# diskohedron4w_revc.net
KiCad netlist of a schematic drawn in EAGLE
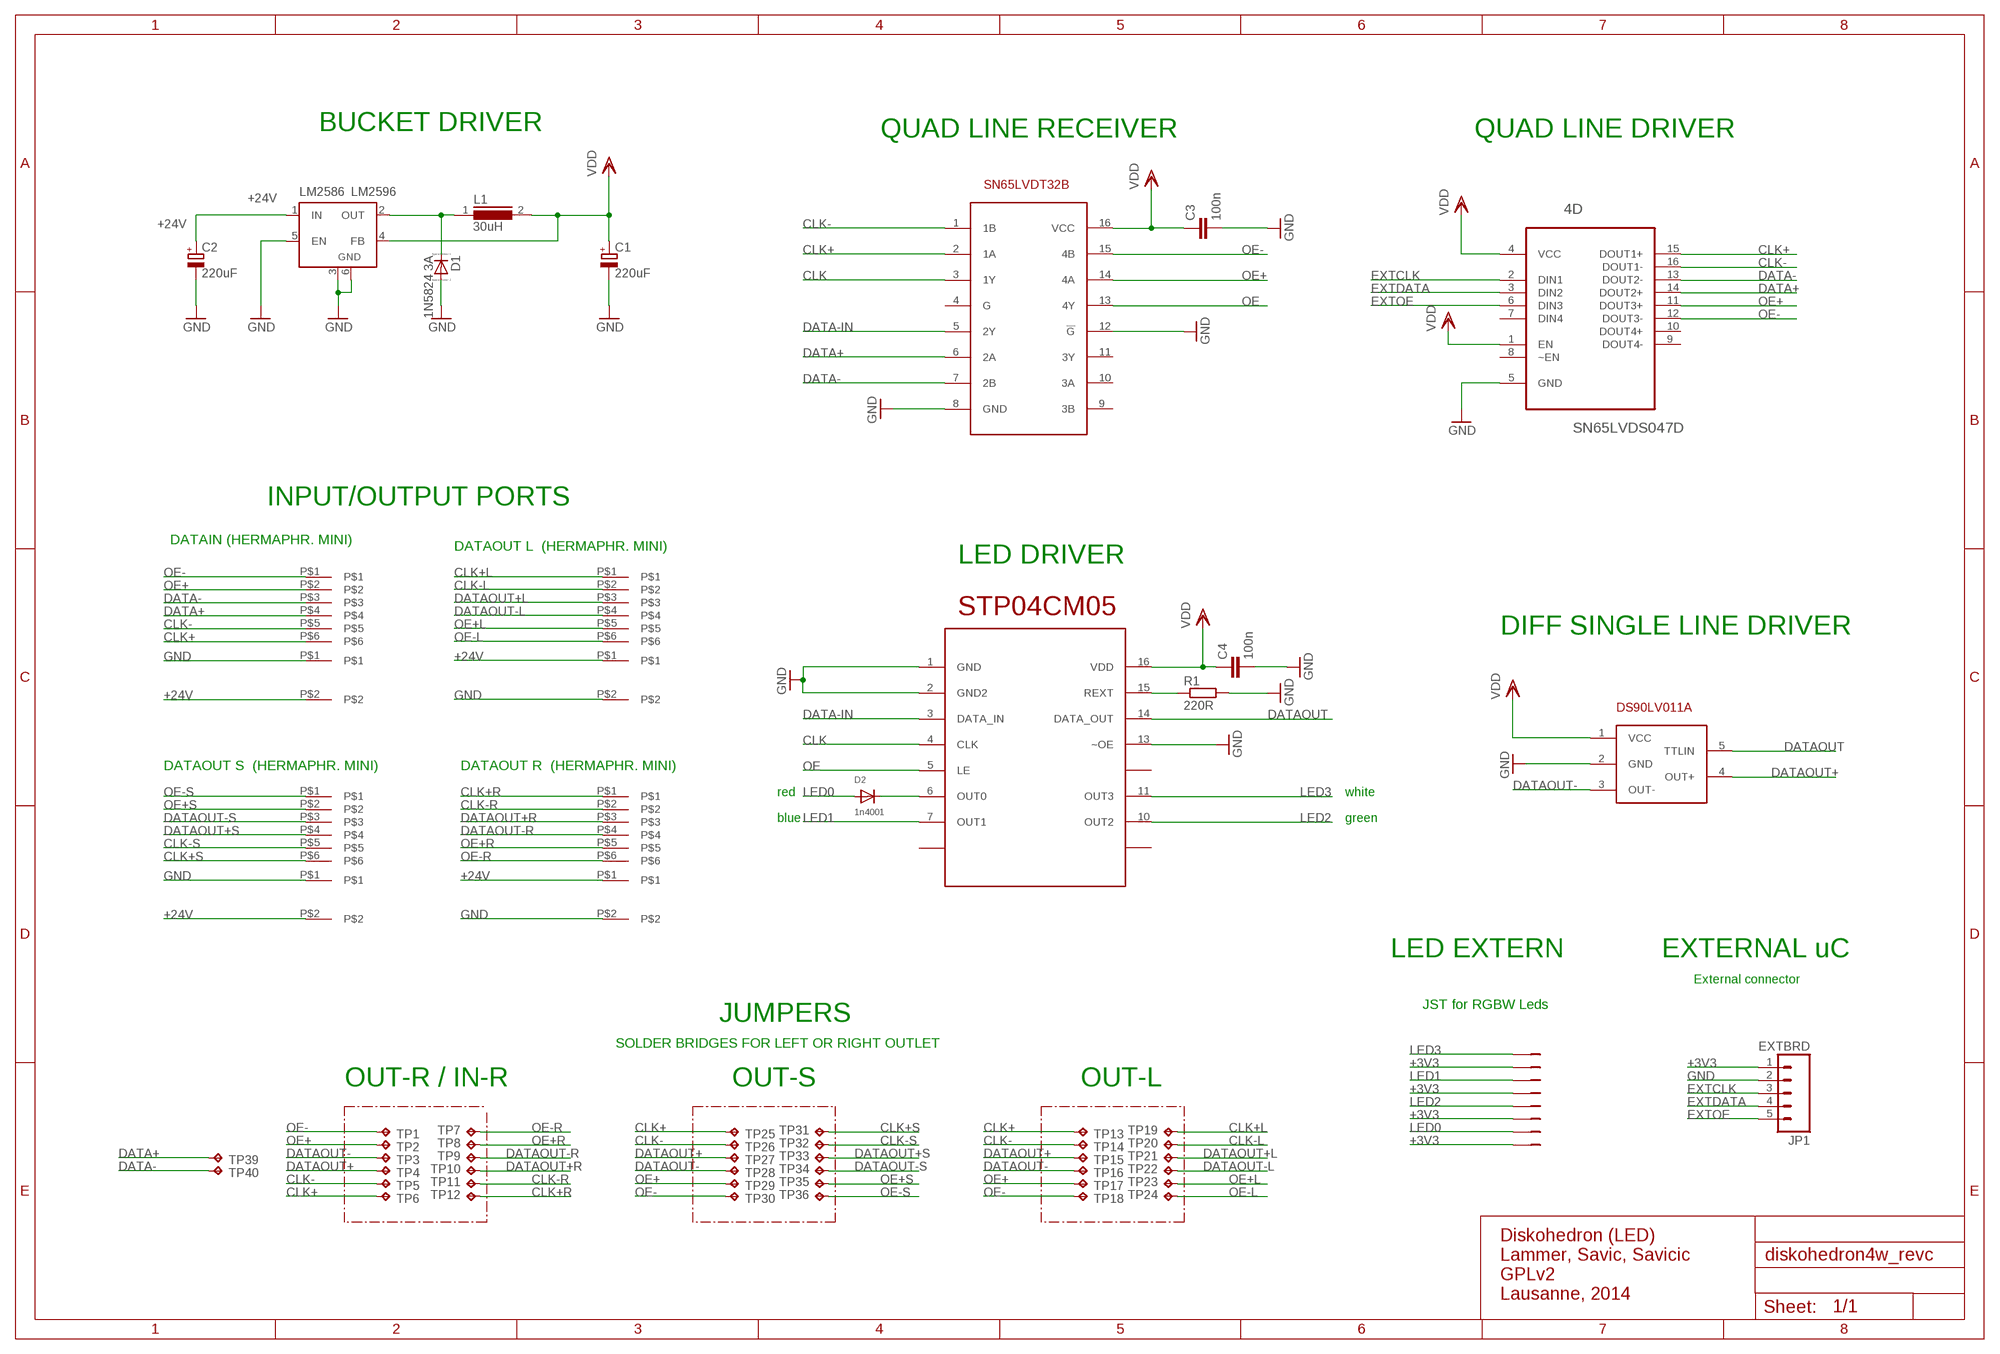
[diagram p0: schematic, sheet 1]

(export (version "E")
  (design (tool "Eeschema 10.0.6"))
  (components
    (comp (ref "1D")
      (value "DS90LV011A")
      (footprint "eagle-import:SOT23-5")
      (libsource (lib "eagle-import") (part "DS90LV011A"))
    )
    (comp (ref "4D")
      (value "SN65LVDS047D")
      (footprint "eagle-import:SOIC127P600X175-16N")
      (libsource (lib "eagle-import") (part "SN65LVDS047D"))
    )
    (comp (ref "4R")
      (value "SN65LVDST32")
      (footprint "eagle-import:SOIC16")
      (libsource (lib "eagle-import") (part "SN65LVDST32"))
    )
    (comp (ref "C1")
      (value "220uF")
      (footprint "eagle-import:175TMP-0810")
      (libsource (lib "eagle-import") (part "CPOL-EU175TMP-0810"))
    )
    (comp (ref "C2")
      (value "220uF")
      (footprint "eagle-import:175TMP-0810")
      (libsource (lib "eagle-import") (part "CPOL-EU175TMP-0810"))
    )
    (comp (ref "C3")
      (value "100n")
      (footprint "eagle-import:C0805")
      (libsource (lib "eagle-import") (part "C-EUC0805"))
    )
    (comp (ref "C4")
      (value "100n")
      (footprint "eagle-import:C0805")
      (libsource (lib "eagle-import") (part "C-EUC0805"))
    )
    (comp (ref "D1")
      (value "1N5824 3A")
      (footprint "eagle-import:DIODE_SMC")
      (libsource (lib "eagle-import") (part "DIODE_E-SMC"))
    )
    (comp (ref "D2")
      (value "1n4001")
      (footprint "eagle-import:SMADIODE")
      (libsource (lib "eagle-import") (part "DIODESMA"))
    )
    (comp (ref "IN1")
      (value "HERMAPHRODITMINI6PIN")
      (footprint "eagle-import:HERMAPHRODITMINI6PIN")
      (libsource (lib "eagle-import") (part "HERMAPHRODITMINI6PIN"))
    )
    (comp (ref "JP1")
      (value "EXTBRD")
      (footprint "eagle-import:1X05")
      (libsource (lib "eagle-import") (part "M05PTH"))
    )
    (comp (ref "JST")
      (value "8PIN-ZH")
      (footprint "eagle-import:B8B-ZH")
      (libsource (lib "eagle-import") (part "8PIN-ZH"))
    )
    (comp (ref "L1")
      (value "30uH")
      (footprint "eagle-import:DR127")
      (libsource (lib "eagle-import") (part "DR127"))
    )
    (comp (ref "LM2586")
      (value "LM2596")
      (footprint "eagle-import:TO263-5")
      (libsource (lib "eagle-import") (part "LM2596S"))
    )
    (comp (ref "OUT-L")
      (value "HERMAPHRODITMINI6PIN")
      (footprint "eagle-import:HERMAPHRODITMINI6PIN")
      (libsource (lib "eagle-import") (part "HERMAPHRODITMINI6PIN"))
    )
    (comp (ref "OUT-R")
      (value "HERMAPHRODITMINI6PIN")
      (footprint "eagle-import:HERMAPHRODITMINI6PIN")
      (libsource (lib "eagle-import") (part "HERMAPHRODITMINI6PIN"))
    )
    (comp (ref "OUT-R1")
      (value "HERMAPHRODITMINI6PIN")
      (footprint "eagle-import:HERMAPHRODITMINI6PIN")
      (libsource (lib "eagle-import") (part "HERMAPHRODITMINI6PIN"))
    )
    (comp (ref "R1")
      (value "220R")
      (footprint "eagle-import:M0805")
      (libsource (lib "eagle-import") (part "R-EU_M0805"))
    )
    (comp (ref "STP04")
      (value "STP04CM05")
      (footprint "eagle-import:TSSOP16")
      (libsource (lib "eagle-import") (part "STP04CM05"))
    )
    (comp (ref "TP1")
      (value "TPTP12SQ")
      (footprint "eagle-import:TP12SQ")
      (libsource (lib "eagle-import") (part "TPTP12SQ"))
    )
    (comp (ref "TP2")
      (value "TPTP12SQ")
      (footprint "eagle-import:TP12SQ")
      (libsource (lib "eagle-import") (part "TPTP12SQ"))
    )
    (comp (ref "TP3")
      (value "TPTP09SQ")
      (footprint "eagle-import:TP09SQ")
      (libsource (lib "eagle-import") (part "TPTP09SQ"))
    )
    (comp (ref "TP4")
      (value "TPTP09SQ")
      (footprint "eagle-import:TP09SQ")
      (libsource (lib "eagle-import") (part "TPTP09SQ"))
    )
    (comp (ref "TP5")
      (value "TPTP12SQ")
      (footprint "eagle-import:TP12SQ")
      (libsource (lib "eagle-import") (part "TPTP12SQ"))
    )
    (comp (ref "TP6")
      (value "TPTP12SQ")
      (footprint "eagle-import:TP12SQ")
      (libsource (lib "eagle-import") (part "TPTP12SQ"))
    )
    (comp (ref "TP7")
      (value "TPTP12SQ")
      (footprint "eagle-import:TP12SQ")
      (libsource (lib "eagle-import") (part "TPTP12SQ"))
    )
    (comp (ref "TP8")
      (value "TPTP12SQ")
      (footprint "eagle-import:TP12SQ")
      (libsource (lib "eagle-import") (part "TPTP12SQ"))
    )
    (comp (ref "TP9")
      (value "TPTP20SQ")
      (footprint "eagle-import:TP20SQ")
      (libsource (lib "eagle-import") (part "TPTP20SQ"))
    )
    (comp (ref "TP10")
      (value "TPTP20SQ")
      (footprint "eagle-import:TP20SQ")
      (libsource (lib "eagle-import") (part "TPTP20SQ"))
    )
    (comp (ref "TP11")
      (value "TPTP12SQ")
      (footprint "eagle-import:TP12SQ")
      (libsource (lib "eagle-import") (part "TPTP12SQ"))
    )
    (comp (ref "TP12")
      (value "TPTP12SQ")
      (footprint "eagle-import:TP12SQ")
      (libsource (lib "eagle-import") (part "TPTP12SQ"))
    )
    (comp (ref "TP13")
      (value "TPTP12SQ")
      (footprint "eagle-import:TP12SQ")
      (libsource (lib "eagle-import") (part "TPTP12SQ"))
    )
    (comp (ref "TP14")
      (value "TPTP12SQ")
      (footprint "eagle-import:TP12SQ")
      (libsource (lib "eagle-import") (part "TPTP12SQ"))
    )
    (comp (ref "TP15")
      (value "TPTP12SQ")
      (footprint "eagle-import:TP12SQ")
      (libsource (lib "eagle-import") (part "TPTP12SQ"))
    )
    (comp (ref "TP16")
      (value "TPTP12SQ")
      (footprint "eagle-import:TP12SQ")
      (libsource (lib "eagle-import") (part "TPTP12SQ"))
    )
    (comp (ref "TP17")
      (value "TPTP12SQ")
      (footprint "eagle-import:TP12SQ")
      (libsource (lib "eagle-import") (part "TPTP12SQ"))
    )
    (comp (ref "TP18")
      (value "TPTP12SQ")
      (footprint "eagle-import:TP12SQ")
      (libsource (lib "eagle-import") (part "TPTP12SQ"))
    )
    (comp (ref "TP19")
      (value "TPTP12SQ")
      (footprint "eagle-import:TP12SQ")
      (libsource (lib "eagle-import") (part "TPTP12SQ"))
    )
    (comp (ref "TP20")
      (value "TPTP12SQ")
      (footprint "eagle-import:TP12SQ")
      (libsource (lib "eagle-import") (part "TPTP12SQ"))
    )
    (comp (ref "TP21")
      (value "TPTP12SQ")
      (footprint "eagle-import:TP12SQ")
      (libsource (lib "eagle-import") (part "TPTP12SQ"))
    )
    (comp (ref "TP22")
      (value "TPTP12SQ")
      (footprint "eagle-import:TP12SQ")
      (libsource (lib "eagle-import") (part "TPTP12SQ"))
    )
    (comp (ref "TP23")
      (value "TPTP12SQ")
      (footprint "eagle-import:TP12SQ")
      (libsource (lib "eagle-import") (part "TPTP12SQ"))
    )
    (comp (ref "TP24")
      (value "TPTP12SQ")
      (footprint "eagle-import:TP12SQ")
      (libsource (lib "eagle-import") (part "TPTP12SQ"))
    )
    (comp (ref "TP25")
      (value "TPTP12SQ")
      (footprint "eagle-import:TP12SQ")
      (libsource (lib "eagle-import") (part "TPTP12SQ"))
    )
    (comp (ref "TP26")
      (value "TPTP12SQ")
      (footprint "eagle-import:TP12SQ")
      (libsource (lib "eagle-import") (part "TPTP12SQ"))
    )
    (comp (ref "TP27")
      (value "TPTP12SQ")
      (footprint "eagle-import:TP12SQ")
      (libsource (lib "eagle-import") (part "TPTP12SQ"))
    )
    (comp (ref "TP28")
      (value "TPTP12SQ")
      (footprint "eagle-import:TP12SQ")
      (libsource (lib "eagle-import") (part "TPTP12SQ"))
    )
    (comp (ref "TP29")
      (value "TPTP12SQ")
      (footprint "eagle-import:TP12SQ")
      (libsource (lib "eagle-import") (part "TPTP12SQ"))
    )
    (comp (ref "TP30")
      (value "TPTP12SQ")
      (footprint "eagle-import:TP12SQ")
      (libsource (lib "eagle-import") (part "TPTP12SQ"))
    )
    (comp (ref "TP31")
      (value "TPTP12SQ")
      (footprint "eagle-import:TP12SQ")
      (libsource (lib "eagle-import") (part "TPTP12SQ"))
    )
    (comp (ref "TP32")
      (value "TPTP12SQ")
      (footprint "eagle-import:TP12SQ")
      (libsource (lib "eagle-import") (part "TPTP12SQ"))
    )
    (comp (ref "TP33")
      (value "TPTP12SQ")
      (footprint "eagle-import:TP12SQ")
      (libsource (lib "eagle-import") (part "TPTP12SQ"))
    )
    (comp (ref "TP34")
      (value "TPTP12SQ")
      (footprint "eagle-import:TP12SQ")
      (libsource (lib "eagle-import") (part "TPTP12SQ"))
    )
    (comp (ref "TP35")
      (value "TPTP12SQ")
      (footprint "eagle-import:TP12SQ")
      (libsource (lib "eagle-import") (part "TPTP12SQ"))
    )
    (comp (ref "TP36")
      (value "TPTP12SQ")
      (footprint "eagle-import:TP12SQ")
      (libsource (lib "eagle-import") (part "TPTP12SQ"))
    )
    (comp (ref "TP39")
      (value "TPTP09SQ")
      (footprint "eagle-import:TP09SQ")
      (libsource (lib "eagle-import") (part "TPTP09SQ"))
    )
    (comp (ref "TP40")
      (value "TPTP09SQ")
      (footprint "eagle-import:TP09SQ")
      (libsource (lib "eagle-import") (part "TPTP09SQ"))
    )
    (comp (ref "U$1")
      (value "HERMAPHRODIT2PIN")
      (footprint "eagle-import:HERMAPHRODIT2PIN")
      (libsource (lib "eagle-import") (part "HERMAPHRODIT2PIN"))
    )
    (comp (ref "U$6")
      (value "HERMAPHRODIT2PIN")
      (footprint "eagle-import:HERMAPHRODIT2PIN")
      (libsource (lib "eagle-import") (part "HERMAPHRODIT2PIN"))
    )
    (comp (ref "U$7")
      (value "HERMAPHRODIT2PIN")
      (footprint "eagle-import:HERMAPHRODIT2PIN")
      (libsource (lib "eagle-import") (part "HERMAPHRODIT2PIN"))
    )
    (comp (ref "U$12")
      (value "HERMAPHRODIT2PIN")
      (footprint "eagle-import:HERMAPHRODIT2PIN")
      (libsource (lib "eagle-import") (part "HERMAPHRODIT2PIN"))
    )
  )
  (nets
    (net (code "1") (name "/+24V") (class "Default")
      (node (ref "C2") (pin "+") (pinfunction "+_+") (pintype "passive"))
      (node (ref "LM2586") (pin "1") (pinfunction "IN_1") (pintype "input"))
      (node (ref "U$1") (pin "P$2") (pinfunction "P$2_P$2") (pintype "bidirectional"))
      (node (ref "U$12") (pin "P$1") (pinfunction "P$1_P$1") (pintype "bidirectional"))
      (node (ref "U$6") (pin "P$1") (pinfunction "P$1_P$1") (pintype "bidirectional"))
      (node (ref "U$7") (pin "P$2") (pinfunction "P$2_P$2") (pintype "bidirectional"))
    )
    (net (code "2") (name "/CLK") (class "Default")
      (node (ref "4R") (pin "3") (pinfunction "1Y_3") (pintype "bidirectional"))
      (node (ref "STP04") (pin "4") (pinfunction "CLK_4") (pintype "bidirectional"))
    )
    (net (code "3") (name "/CLK+") (class "Default")
      (node (ref "4D") (pin "15") (pinfunction "DOUT1+_15") (pintype "output"))
      (node (ref "4R") (pin "2") (pinfunction "1A_2") (pintype "bidirectional"))
      (node (ref "IN1") (pin "P$6") (pinfunction "P$6_P$6") (pintype "bidirectional"))
      (node (ref "TP13") (pin "TP") (pinfunction "TP_TP") (pintype "input"))
      (node (ref "TP25") (pin "TP") (pinfunction "TP_TP") (pintype "input"))
      (node (ref "TP6") (pin "TP") (pinfunction "TP_TP") (pintype "input"))
    )
    (net (code "4") (name "/CLK+L") (class "Default")
      (node (ref "OUT-L") (pin "P$1") (pinfunction "P$1_P$1") (pintype "bidirectional"))
      (node (ref "TP19") (pin "TP") (pinfunction "TP_TP") (pintype "input"))
    )
    (net (code "5") (name "/CLK+R") (class "Default")
      (node (ref "OUT-R") (pin "P$1") (pinfunction "P$1_P$1") (pintype "bidirectional"))
      (node (ref "TP12") (pin "TP") (pinfunction "TP_TP") (pintype "input"))
    )
    (net (code "6") (name "/CLK+S") (class "Default")
      (node (ref "OUT-R1") (pin "P$6") (pinfunction "P$6_P$6") (pintype "bidirectional"))
      (node (ref "TP31") (pin "TP") (pinfunction "TP_TP") (pintype "input"))
    )
    (net (code "7") (name "/CLK-") (class "Default")
      (node (ref "4D") (pin "16") (pinfunction "DOUT1-_16") (pintype "output"))
      (node (ref "4R") (pin "1") (pinfunction "1B_1") (pintype "bidirectional"))
      (node (ref "IN1") (pin "P$5") (pinfunction "P$5_P$5") (pintype "bidirectional"))
      (node (ref "TP14") (pin "TP") (pinfunction "TP_TP") (pintype "input"))
      (node (ref "TP26") (pin "TP") (pinfunction "TP_TP") (pintype "input"))
      (node (ref "TP5") (pin "TP") (pinfunction "TP_TP") (pintype "input"))
    )
    (net (code "8") (name "/CLK-L") (class "Default")
      (node (ref "OUT-L") (pin "P$2") (pinfunction "P$2_P$2") (pintype "bidirectional"))
      (node (ref "TP20") (pin "TP") (pinfunction "TP_TP") (pintype "input"))
    )
    (net (code "9") (name "/CLK-R") (class "Default")
      (node (ref "OUT-R") (pin "P$2") (pinfunction "P$2_P$2") (pintype "bidirectional"))
      (node (ref "TP11") (pin "TP") (pinfunction "TP_TP") (pintype "input"))
    )
    (net (code "10") (name "/CLK-S") (class "Default")
      (node (ref "OUT-R1") (pin "P$5") (pinfunction "P$5_P$5") (pintype "bidirectional"))
      (node (ref "TP32") (pin "TP") (pinfunction "TP_TP") (pintype "input"))
    )
    (net (code "11") (name "/DATA+") (class "Default")
      (node (ref "4D") (pin "14") (pinfunction "DOUT2+_14") (pintype "output"))
      (node (ref "4R") (pin "6") (pinfunction "2A_6") (pintype "bidirectional"))
      (node (ref "IN1") (pin "P$4") (pinfunction "P$4_P$4") (pintype "bidirectional"))
      (node (ref "TP39") (pin "TP") (pinfunction "TP_TP") (pintype "input"))
    )
    (net (code "12") (name "/DATA-") (class "Default")
      (node (ref "4D") (pin "13") (pinfunction "DOUT2-_13") (pintype "output"))
      (node (ref "4R") (pin "7") (pinfunction "2B_7") (pintype "bidirectional"))
      (node (ref "IN1") (pin "P$3") (pinfunction "P$3_P$3") (pintype "bidirectional"))
      (node (ref "TP40") (pin "TP") (pinfunction "TP_TP") (pintype "input"))
    )
    (net (code "13") (name "/DATA-IN") (class "Default")
      (node (ref "4R") (pin "5") (pinfunction "2Y_5") (pintype "bidirectional"))
      (node (ref "STP04") (pin "3") (pinfunction "DATA_IN_3") (pintype "bidirectional"))
    )
    (net (code "14") (name "/DATAOUT") (class "Default")
      (node (ref "1D") (pin "5") (pinfunction "TTLIN_5") (pintype "bidirectional"))
      (node (ref "STP04") (pin "14") (pinfunction "DATA_OUT_14") (pintype "bidirectional"))
    )
    (net (code "15") (name "/DATAOUT+") (class "Default")
      (node (ref "1D") (pin "4") (pinfunction "OUT+_4") (pintype "bidirectional"))
      (node (ref "TP15") (pin "TP") (pinfunction "TP_TP") (pintype "input"))
      (node (ref "TP27") (pin "TP") (pinfunction "TP_TP") (pintype "input"))
      (node (ref "TP4") (pin "TP") (pinfunction "TP_TP") (pintype "input"))
    )
    (net (code "16") (name "/DATAOUT+L") (class "Default")
      (node (ref "OUT-L") (pin "P$3") (pinfunction "P$3_P$3") (pintype "bidirectional"))
      (node (ref "TP21") (pin "TP") (pinfunction "TP_TP") (pintype "input"))
    )
    (net (code "17") (name "/DATAOUT+R") (class "Default")
      (node (ref "OUT-R") (pin "P$3") (pinfunction "P$3_P$3") (pintype "bidirectional"))
      (node (ref "TP10") (pin "TP") (pinfunction "TP_TP") (pintype "input"))
    )
    (net (code "18") (name "/DATAOUT+S") (class "Default")
      (node (ref "OUT-R1") (pin "P$4") (pinfunction "P$4_P$4") (pintype "bidirectional"))
      (node (ref "TP33") (pin "TP") (pinfunction "TP_TP") (pintype "input"))
    )
    (net (code "19") (name "/DATAOUT-") (class "Default")
      (node (ref "1D") (pin "3") (pinfunction "OUT-_3") (pintype "bidirectional"))
      (node (ref "TP16") (pin "TP") (pinfunction "TP_TP") (pintype "input"))
      (node (ref "TP28") (pin "TP") (pinfunction "TP_TP") (pintype "input"))
      (node (ref "TP3") (pin "TP") (pinfunction "TP_TP") (pintype "input"))
    )
    (net (code "20") (name "/DATAOUT-L") (class "Default")
      (node (ref "OUT-L") (pin "P$4") (pinfunction "P$4_P$4") (pintype "bidirectional"))
      (node (ref "TP22") (pin "TP") (pinfunction "TP_TP") (pintype "input"))
    )
    (net (code "21") (name "/DATAOUT-R") (class "Default")
      (node (ref "OUT-R") (pin "P$4") (pinfunction "P$4_P$4") (pintype "bidirectional"))
      (node (ref "TP9") (pin "TP") (pinfunction "TP_TP") (pintype "input"))
    )
    (net (code "22") (name "/DATAOUT-S") (class "Default")
      (node (ref "OUT-R1") (pin "P$3") (pinfunction "P$3_P$3") (pintype "bidirectional"))
      (node (ref "TP34") (pin "TP") (pinfunction "TP_TP") (pintype "input"))
    )
    (net (code "23") (name "/EXTCLK") (class "Default")
      (node (ref "4D") (pin "2") (pinfunction "DIN1_2") (pintype "input"))
      (node (ref "JP1") (pin "3") (pinfunction "3_3") (pintype "passive"))
    )
    (net (code "24") (name "/EXTDATA") (class "Default")
      (node (ref "4D") (pin "3") (pinfunction "DIN2_3") (pintype "input"))
      (node (ref "JP1") (pin "4") (pinfunction "4_4") (pintype "passive"))
    )
    (net (code "25") (name "/EXTOE") (class "Default")
      (node (ref "4D") (pin "6") (pinfunction "DIN3_6") (pintype "input"))
      (node (ref "JP1") (pin "5") (pinfunction "5_5") (pintype "passive"))
    )
    (net (code "26") (name "/LED0") (class "Default")
      (node (ref "D2") (pin "A") (pinfunction "A_A") (pintype "passive"))
      (node (ref "JST") (pin "7") (pinfunction "1_7") (pintype "passive"))
    )
    (net (code "27") (name "/LED1") (class "Default")
      (node (ref "JST") (pin "3") (pinfunction "1_3") (pintype "passive"))
      (node (ref "STP04") (pin "7") (pinfunction "OUT1_7") (pintype "bidirectional"))
    )
    (net (code "28") (name "/LED2") (class "Default")
      (node (ref "JST") (pin "5") (pinfunction "1_5") (pintype "passive"))
      (node (ref "STP04") (pin "10") (pinfunction "OUT2_10") (pintype "bidirectional"))
    )
    (net (code "29") (name "/LED3") (class "Default")
      (node (ref "JST") (pin "1") (pinfunction "1_1") (pintype "passive"))
      (node (ref "STP04") (pin "11") (pinfunction "OUT3_11") (pintype "bidirectional"))
    )
    (net (code "30") (name "/OE") (class "Default")
      (node (ref "4R") (pin "13") (pinfunction "4Y_13") (pintype "bidirectional"))
      (node (ref "STP04") (pin "5") (pinfunction "LE_5") (pintype "bidirectional"))
    )
    (net (code "31") (name "/OE+") (class "Default")
      (node (ref "4D") (pin "11") (pinfunction "DOUT3+_11") (pintype "output"))
      (node (ref "4R") (pin "14") (pinfunction "4A_14") (pintype "bidirectional"))
      (node (ref "IN1") (pin "P$2") (pinfunction "P$2_P$2") (pintype "bidirectional"))
      (node (ref "TP17") (pin "TP") (pinfunction "TP_TP") (pintype "input"))
      (node (ref "TP2") (pin "TP") (pinfunction "TP_TP") (pintype "input"))
      (node (ref "TP29") (pin "TP") (pinfunction "TP_TP") (pintype "input"))
    )
    (net (code "32") (name "/OE+L") (class "Default")
      (node (ref "OUT-L") (pin "P$5") (pinfunction "P$5_P$5") (pintype "bidirectional"))
      (node (ref "TP23") (pin "TP") (pinfunction "TP_TP") (pintype "input"))
    )
    (net (code "33") (name "/OE+R") (class "Default")
      (node (ref "OUT-R") (pin "P$5") (pinfunction "P$5_P$5") (pintype "bidirectional"))
      (node (ref "TP8") (pin "TP") (pinfunction "TP_TP") (pintype "input"))
    )
    (net (code "34") (name "/OE+S") (class "Default")
      (node (ref "OUT-R1") (pin "P$2") (pinfunction "P$2_P$2") (pintype "bidirectional"))
      (node (ref "TP35") (pin "TP") (pinfunction "TP_TP") (pintype "input"))
    )
    (net (code "35") (name "/OE-") (class "Default")
      (node (ref "4D") (pin "12") (pinfunction "DOUT3-_12") (pintype "output"))
      (node (ref "4R") (pin "15") (pinfunction "4B_15") (pintype "bidirectional"))
      (node (ref "IN1") (pin "P$1") (pinfunction "P$1_P$1") (pintype "bidirectional"))
      (node (ref "TP1") (pin "TP") (pinfunction "TP_TP") (pintype "input"))
      (node (ref "TP18") (pin "TP") (pinfunction "TP_TP") (pintype "input"))
      (node (ref "TP30") (pin "TP") (pinfunction "TP_TP") (pintype "input"))
    )
    (net (code "36") (name "/OE-L") (class "Default")
      (node (ref "OUT-L") (pin "P$6") (pinfunction "P$6_P$6") (pintype "bidirectional"))
      (node (ref "TP24") (pin "TP") (pinfunction "TP_TP") (pintype "input"))
    )
    (net (code "37") (name "/OE-R") (class "Default")
      (node (ref "OUT-R") (pin "P$6") (pinfunction "P$6_P$6") (pintype "bidirectional"))
      (node (ref "TP7") (pin "TP") (pinfunction "TP_TP") (pintype "input"))
    )
    (net (code "38") (name "/OE-S") (class "Default")
      (node (ref "OUT-R1") (pin "P$1") (pinfunction "P$1_P$1") (pintype "bidirectional"))
      (node (ref "TP36") (pin "TP") (pinfunction "TP_TP") (pintype "input"))
    )
    (net (code "39") (name "GND") (class "Default")
      (node (ref "1D") (pin "2") (pinfunction "GND_2") (pintype "bidirectional"))
      (node (ref "4D") (pin "5") (pinfunction "GND_5") (pintype "passive"))
      (node (ref "4R") (pin "12") (pinfunction "~{G}_12") (pintype "bidirectional"))
      (node (ref "4R") (pin "8") (pinfunction "GND_8") (pintype "bidirectional"))
      (node (ref "C1") (pin "-") (pinfunction "-_-") (pintype "passive"))
      (node (ref "C2") (pin "-") (pinfunction "-_-") (pintype "passive"))
      (node (ref "C3") (pin "2") (pinfunction "2_2") (pintype "passive"))
      (node (ref "C4") (pin "2") (pinfunction "2_2") (pintype "passive"))
      (node (ref "D1") (pin "A") (pinfunction "C_A") (pintype "passive"))
      (node (ref "JP1") (pin "2") (pinfunction "2_2") (pintype "passive"))
      (node (ref "LM2586") (pin "3") (pinfunction "GND_3") (pintype "power_in"))
      (node (ref "LM2586") (pin "5") (pinfunction "EN_5") (pintype "input"))
      (node (ref "LM2586") (pin "6") (pinfunction "GND_6") (pintype "power_in"))
      (node (ref "R1") (pin "2") (pinfunction "2_2") (pintype "passive"))
      (node (ref "STP04") (pin "1") (pinfunction "GND_1") (pintype "bidirectional"))
      (node (ref "STP04") (pin "13") (pinfunction "~{OE}_13") (pintype "bidirectional"))
      (node (ref "STP04") (pin "2") (pinfunction "GND2_2") (pintype "bidirectional"))
      (node (ref "U$1") (pin "P$1") (pinfunction "P$1_P$1") (pintype "bidirectional"))
      (node (ref "U$12") (pin "P$2") (pinfunction "P$2_P$2") (pintype "bidirectional"))
      (node (ref "U$6") (pin "P$2") (pinfunction "P$2_P$2") (pintype "bidirectional"))
      (node (ref "U$7") (pin "P$1") (pinfunction "P$1_P$1") (pintype "bidirectional"))
    )
    (net (code "40") (name "Net-(D1-A)") (class "Default")
      (node (ref "D1") (pin "C") (pinfunction "A_C") (pintype "passive"))
      (node (ref "L1") (pin "1") (pinfunction "1_1") (pintype "passive"))
      (node (ref "LM2586") (pin "2") (pinfunction "OUT_2") (pintype "output"))
    )
    (net (code "41") (name "Net-(STP04-OUT0)") (class "Default")
      (node (ref "D2") (pin "C") (pinfunction "C_C") (pintype "passive"))
      (node (ref "STP04") (pin "6") (pinfunction "OUT0_6") (pintype "bidirectional"))
    )
    (net (code "42") (name "Net-(STP04-REXT)") (class "Default")
      (node (ref "R1") (pin "1") (pinfunction "1_1") (pintype "passive"))
      (node (ref "STP04") (pin "15") (pinfunction "REXT_15") (pintype "bidirectional"))
    )
    (net (code "43") (name "VDD") (class "Default")
      (node (ref "1D") (pin "1") (pinfunction "VCC_1") (pintype "bidirectional"))
      (node (ref "4D") (pin "1") (pinfunction "EN_1") (pintype "input"))
      (node (ref "4D") (pin "4") (pinfunction "VCC_4") (pintype "power_in"))
      (node (ref "4R") (pin "16") (pinfunction "VCC_16") (pintype "bidirectional"))
      (node (ref "C1") (pin "+") (pinfunction "+_+") (pintype "passive"))
      (node (ref "C3") (pin "1") (pinfunction "1_1") (pintype "passive"))
      (node (ref "C4") (pin "1") (pinfunction "1_1") (pintype "passive"))
      (node (ref "JP1") (pin "1") (pinfunction "1_1") (pintype "passive"))
      (node (ref "JST") (pin "2") (pinfunction "1_2") (pintype "passive"))
      (node (ref "JST") (pin "4") (pinfunction "1_4") (pintype "passive"))
      (node (ref "JST") (pin "6") (pinfunction "1_6") (pintype "passive"))
      (node (ref "JST") (pin "8") (pinfunction "1_8") (pintype "passive"))
      (node (ref "L1") (pin "2") (pinfunction "2_2") (pintype "passive"))
      (node (ref "LM2586") (pin "4") (pinfunction "FB_4") (pintype "input"))
      (node (ref "STP04") (pin "16") (pinfunction "VDD_16") (pintype "bidirectional"))
    )
    (net (code "44") (name "unconnected-(4D-DIN4-Pad7)") (class "Default")
      (node (ref "4D") (pin "7") (pinfunction "DIN4_7") (pintype "input"))
    )
    (net (code "45") (name "unconnected-(4D-DOUT4+-Pad10)") (class "Default")
      (node (ref "4D") (pin "10") (pinfunction "DOUT4+_10") (pintype "output"))
    )
    (net (code "46") (name "unconnected-(4D-DOUT4--Pad9)") (class "Default")
      (node (ref "4D") (pin "9") (pinfunction "DOUT4-_9") (pintype "output"))
    )
    (net (code "47") (name "unconnected-(4D-~{EN}-Pad8)") (class "Default")
      (node (ref "4D") (pin "8") (pinfunction "~{EN}_8") (pintype "input"))
    )
    (net (code "48") (name "unconnected-(4R-3A-Pad10)") (class "Default")
      (node (ref "4R") (pin "10") (pinfunction "3A_10") (pintype "bidirectional"))
    )
    (net (code "49") (name "unconnected-(4R-3B-Pad9)") (class "Default")
      (node (ref "4R") (pin "9") (pinfunction "3B_9") (pintype "bidirectional"))
    )
    (net (code "50") (name "unconnected-(4R-3Y-Pad11)") (class "Default")
      (node (ref "4R") (pin "11") (pinfunction "3Y_11") (pintype "bidirectional"))
    )
    (net (code "51") (name "unconnected-(4R-G-Pad4)") (class "Default")
      (node (ref "4R") (pin "4") (pinfunction "G_4") (pintype "bidirectional"))
    )
    (net (code "52") (name "unconnected-(STP04-N.C1-Pad8)") (class "Default")
      (node (ref "STP04") (pin "8") (pinfunction "N.C1_8") (pintype "bidirectional"))
    )
    (net (code "53") (name "unconnected-(STP04-NC-Pad9)") (class "Default")
      (node (ref "STP04") (pin "9") (pinfunction "NC_9") (pintype "bidirectional"))
    )
    (net (code "54") (name "unconnected-(STP04-NC3-Pad12)") (class "Default")
      (node (ref "STP04") (pin "12") (pinfunction "NC3_12") (pintype "bidirectional"))
    )
  )
)
